# Arduino__Connectors.net
KiCad netlist of a schematic drawn in Altium Designer
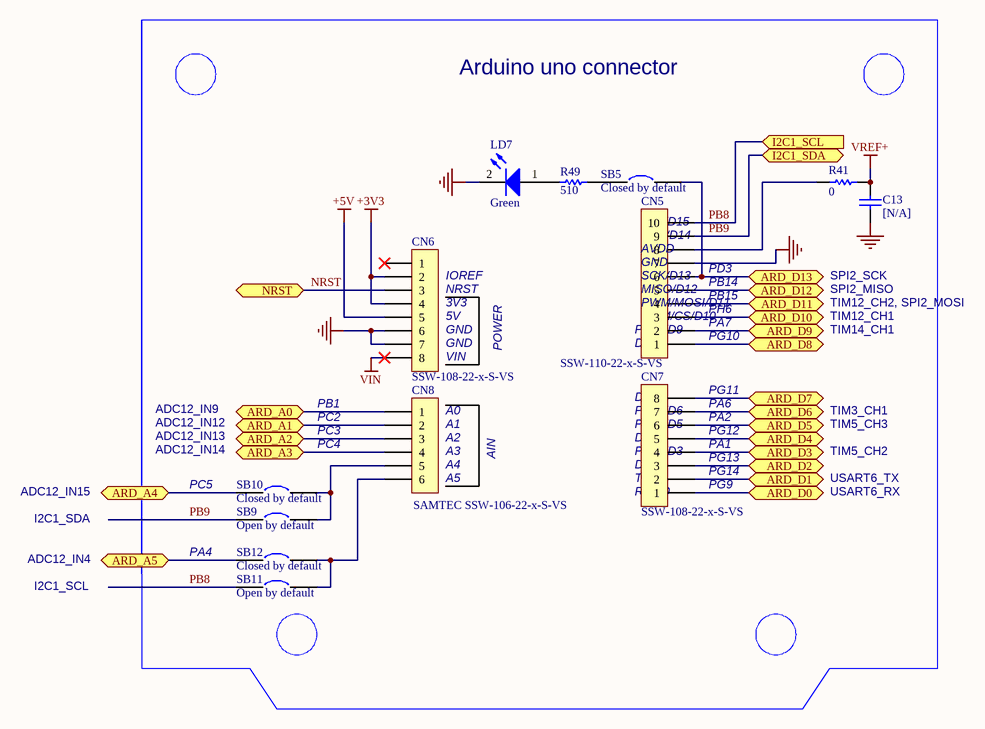
[diagram p0: Arduino_ Connectors.SchDoc]

(export (version "E")
  (design (tool "Eeschema 10.0.6"))
  (components
    (comp (ref "C13")
      (value "[N/A]")
      (footprint "0603C")
      (description "Capacitor")
      (fields (field (name "PUBLISHER") "Altium Limited"))
      (libsource (lib "Miscellaneous Devices") (part "Cap"))
    )
    (comp (ref "CN5")
      (value "SSW-110-22-x-S-VS")
      (footprint "SSW-110-22-X-S-VS")
      (description "Header, 10-Pin, Single row,female")
      (fields (field (name "PUBLISHER") "Altium Limited"))
      (libsource (lib "Nucleo_64") (part "Header 10X1_Female"))
    )
    (comp (ref "CN6")
      (value "SSW-108-22-x-S-VS")
      (footprint "SSW-108-22-X-S-VS")
      (description "Header, 8-Pin, Single row,female")
      (fields (field (name "PUBLISHER") "Altium Limited"))
      (libsource (lib "") (part "Header 8X1_Female_1"))
    )
    (comp (ref "CN7")
      (value "SSW-108-22-x-S-VS")
      (footprint "SSW-108-22-X-S-VS")
      (description "Header, 8-Pin, Single row,female")
      (fields (field (name "PUBLISHER") "Altium Limited"))
      (libsource (lib "Nucleo_64") (part "Header 8X1_Female"))
    )
    (comp (ref "CN8")
      (value "SAMTEC SSW-106-22-x-S-VS")
      (footprint "SSW-106-22-X-S-VS")
      (description "Header, 6-Pin, Single row,female SMD")
      (fields (field (name "PUBLISHER") "Altium Limited"))
      (libsource (lib "Nucleo_64") (part "Header 6X1_Female"))
    )
    (comp (ref "LD7")
      (value "Green")
      (footprint "0603D")
      (description "Typical RED, GREEN, YELLOW, AMBER GaAs LED")
      (fields (field (name "PUBLISHER") "Altium Limited"))
      (libsource (lib "Miscellaneous Devices") (part "LED2"))
    )
    (comp (ref "R41")
      (value "0")
      (footprint "0603R")
      (description "Resistor")
      (fields (field (name "PUBLISHER") "Altium Limited"))
      (libsource (lib "Miscellaneous Devices") (part "Res1"))
    )
    (comp (ref "R49")
      (value "510")
      (footprint "0603R")
      (description "Resistor")
      (fields (field (name "PUBLISHER") "Altium Limited"))
      (libsource (lib "Miscellaneous Devices") (part "Res1"))
    )
    (comp (ref "SB5")
      (value "Closed by default")
      (footprint "SB_0603")
      (description "Circuit Breaker")
      (fields (field (name "PUBLISHER") "Altium Limited"))
      (libsource (lib "Miscellaneous Devices") (part "Circuit Breaker"))
    )
    (comp (ref "SB9")
      (value "Open by default")
      (footprint "SB_0603")
      (description "Circuit Breaker")
      (fields (field (name "PUBLISHER") "Altium Limited"))
      (libsource (lib "Miscellaneous Devices") (part "Circuit Breaker"))
    )
    (comp (ref "SB10")
      (value "Closed by default")
      (footprint "SB_0603")
      (description "Circuit Breaker")
      (fields (field (name "PUBLISHER") "Altium Limited"))
      (libsource (lib "Miscellaneous Devices") (part "Circuit Breaker"))
    )
    (comp (ref "SB11")
      (value "Open by default")
      (footprint "SB_0603")
      (description "Circuit Breaker")
      (fields (field (name "PUBLISHER") "Altium Limited"))
      (libsource (lib "Miscellaneous Devices") (part "Circuit Breaker"))
    )
    (comp (ref "SB12")
      (value "Closed by default")
      (footprint "SB_0603")
      (description "Circuit Breaker")
      (fields (field (name "PUBLISHER") "Altium Limited"))
      (libsource (lib "Miscellaneous Devices") (part "Circuit Breaker"))
    )
  )
  (nets
    (net (code "1") (name "+3V3") (class "Default")
      (node (ref "CN6") (pin "2") (pinfunction "2_2") (pintype "passive"))
      (node (ref "CN6") (pin "4") (pinfunction "4_4") (pintype "passive"))
    )
    (net (code "2") (name "+5V") (class "Default")
      (node (ref "CN6") (pin "5") (pinfunction "5_5") (pintype "passive"))
    )
    (net (code "3") (name "/ARD_A0") (class "Default")
      (node (ref "CN8") (pin "1") (pinfunction "1_1") (pintype "passive"))
    )
    (net (code "4") (name "/ARD_A1") (class "Default")
      (node (ref "CN8") (pin "2") (pinfunction "2_2") (pintype "passive"))
    )
    (net (code "5") (name "/ARD_A2") (class "Default")
      (node (ref "CN8") (pin "3") (pinfunction "3_3") (pintype "passive"))
    )
    (net (code "6") (name "/ARD_A3") (class "Default")
      (node (ref "CN8") (pin "4") (pinfunction "4_4") (pintype "passive"))
    )
    (net (code "7") (name "/ARD_A4") (class "Default")
      (node (ref "SB10") (pin "1") (pinfunction "1_1") (pintype "passive"))
    )
    (net (code "8") (name "/ARD_A5") (class "Default")
      (node (ref "SB12") (pin "1") (pinfunction "1_1") (pintype "passive"))
    )
    (net (code "9") (name "/ARD_D0") (class "Default")
      (node (ref "CN7") (pin "1") (pinfunction "1_1") (pintype "passive"))
    )
    (net (code "10") (name "/ARD_D1") (class "Default")
      (node (ref "CN7") (pin "2") (pinfunction "2_2") (pintype "passive"))
    )
    (net (code "11") (name "/ARD_D2") (class "Default")
      (node (ref "CN7") (pin "3") (pinfunction "3_3") (pintype "passive"))
    )
    (net (code "12") (name "/ARD_D3") (class "Default")
      (node (ref "CN7") (pin "4") (pinfunction "4_4") (pintype "passive"))
    )
    (net (code "13") (name "/ARD_D4") (class "Default")
      (node (ref "CN7") (pin "5") (pinfunction "5_5") (pintype "passive"))
    )
    (net (code "14") (name "/ARD_D5") (class "Default")
      (node (ref "CN7") (pin "6") (pinfunction "6_6") (pintype "passive"))
    )
    (net (code "15") (name "/ARD_D6") (class "Default")
      (node (ref "CN7") (pin "7") (pinfunction "7_7") (pintype "passive"))
    )
    (net (code "16") (name "/ARD_D7") (class "Default")
      (node (ref "CN7") (pin "8") (pinfunction "8_8") (pintype "passive"))
    )
    (net (code "17") (name "/ARD_D8") (class "Default")
      (node (ref "CN5") (pin "1") (pinfunction "1_1") (pintype "passive"))
    )
    (net (code "18") (name "/ARD_D9") (class "Default")
      (node (ref "CN5") (pin "2") (pinfunction "2_2") (pintype "passive"))
    )
    (net (code "19") (name "/ARD_D10") (class "Default")
      (node (ref "CN5") (pin "3") (pinfunction "3_3") (pintype "passive"))
    )
    (net (code "20") (name "/ARD_D11") (class "Default")
      (node (ref "CN5") (pin "4") (pinfunction "4_4") (pintype "passive"))
    )
    (net (code "21") (name "/ARD_D12") (class "Default")
      (node (ref "CN5") (pin "5") (pinfunction "5_5") (pintype "passive"))
    )
    (net (code "22") (name "/ARD_D13") (class "Default")
      (node (ref "CN5") (pin "6") (pinfunction "6_6") (pintype "passive"))
      (node (ref "SB5") (pin "2") (pinfunction "2_2") (pintype "passive"))
    )
    (net (code "23") (name "/NRST") (class "Default")
      (node (ref "CN6") (pin "3") (pinfunction "3_3") (pintype "passive"))
    )
    (net (code "24") (name "/PB8") (class "Default")
      (node (ref "CN5") (pin "10") (pinfunction "10_10") (pintype "passive"))
      (node (ref "SB11") (pin "1") (pinfunction "1_1") (pintype "passive"))
    )
    (net (code "25") (name "/PB9") (class "Default")
      (node (ref "CN5") (pin "9") (pinfunction "9_9") (pintype "passive"))
      (node (ref "SB9") (pin "1") (pinfunction "1_1") (pintype "passive"))
    )
    (net (code "26") (name "GND") (class "Default")
      (node (ref "C13") (pin "1") (pinfunction "1_1") (pintype "passive"))
      (node (ref "CN5") (pin "7") (pinfunction "7_7") (pintype "passive"))
      (node (ref "CN6") (pin "6") (pinfunction "6_6") (pintype "passive"))
      (node (ref "CN6") (pin "7") (pinfunction "7_7") (pintype "passive"))
      (node (ref "LD7") (pin "2") (pinfunction "K_2") (pintype "passive"))
    )
    (net (code "27") (name "Net-(CN5-Pad8)") (class "Default")
      (node (ref "CN5") (pin "8") (pinfunction "8_8") (pintype "passive"))
      (node (ref "R41") (pin "2") (pinfunction "2_2") (pintype "passive"))
    )
    (net (code "28") (name "Net-(CN8-Pad5)") (class "Default")
      (node (ref "CN8") (pin "5") (pinfunction "5_5") (pintype "passive"))
      (node (ref "SB10") (pin "2") (pinfunction "2_2") (pintype "passive"))
      (node (ref "SB9") (pin "2") (pinfunction "2_2") (pintype "passive"))
    )
    (net (code "29") (name "Net-(CN8-Pad6)") (class "Default")
      (node (ref "CN8") (pin "6") (pinfunction "6_6") (pintype "passive"))
      (node (ref "SB11") (pin "2") (pinfunction "2_2") (pintype "passive"))
      (node (ref "SB12") (pin "2") (pinfunction "2_2") (pintype "passive"))
    )
    (net (code "30") (name "Net-(LD7-A)") (class "Default")
      (node (ref "LD7") (pin "1") (pinfunction "A_1") (pintype "passive"))
      (node (ref "R49") (pin "2") (pinfunction "2_2") (pintype "passive"))
    )
    (net (code "31") (name "Net-(R49-Pad1)") (class "Default")
      (node (ref "R49") (pin "1") (pinfunction "1_1") (pintype "passive"))
      (node (ref "SB5") (pin "1") (pinfunction "1_1") (pintype "passive"))
    )
    (net (code "32") (name "VIN") (class "Default")
      (node (ref "CN6") (pin "8") (pinfunction "8_8") (pintype "passive"))
    )
    (net (code "33") (name "VREF+") (class "Default")
      (node (ref "C13") (pin "2") (pinfunction "2_2") (pintype "passive"))
      (node (ref "R41") (pin "1") (pinfunction "1_1") (pintype "passive"))
    )
    (net (code "34") (name "unconnected-(CN6-Pad1)") (class "Default")
      (node (ref "CN6") (pin "1") (pinfunction "1_1") (pintype "passive+no_connect"))
    )
  )
)
